# DS131-1_0-BpH.net
KiCad netlist of a schematic drawn in Altium Designer
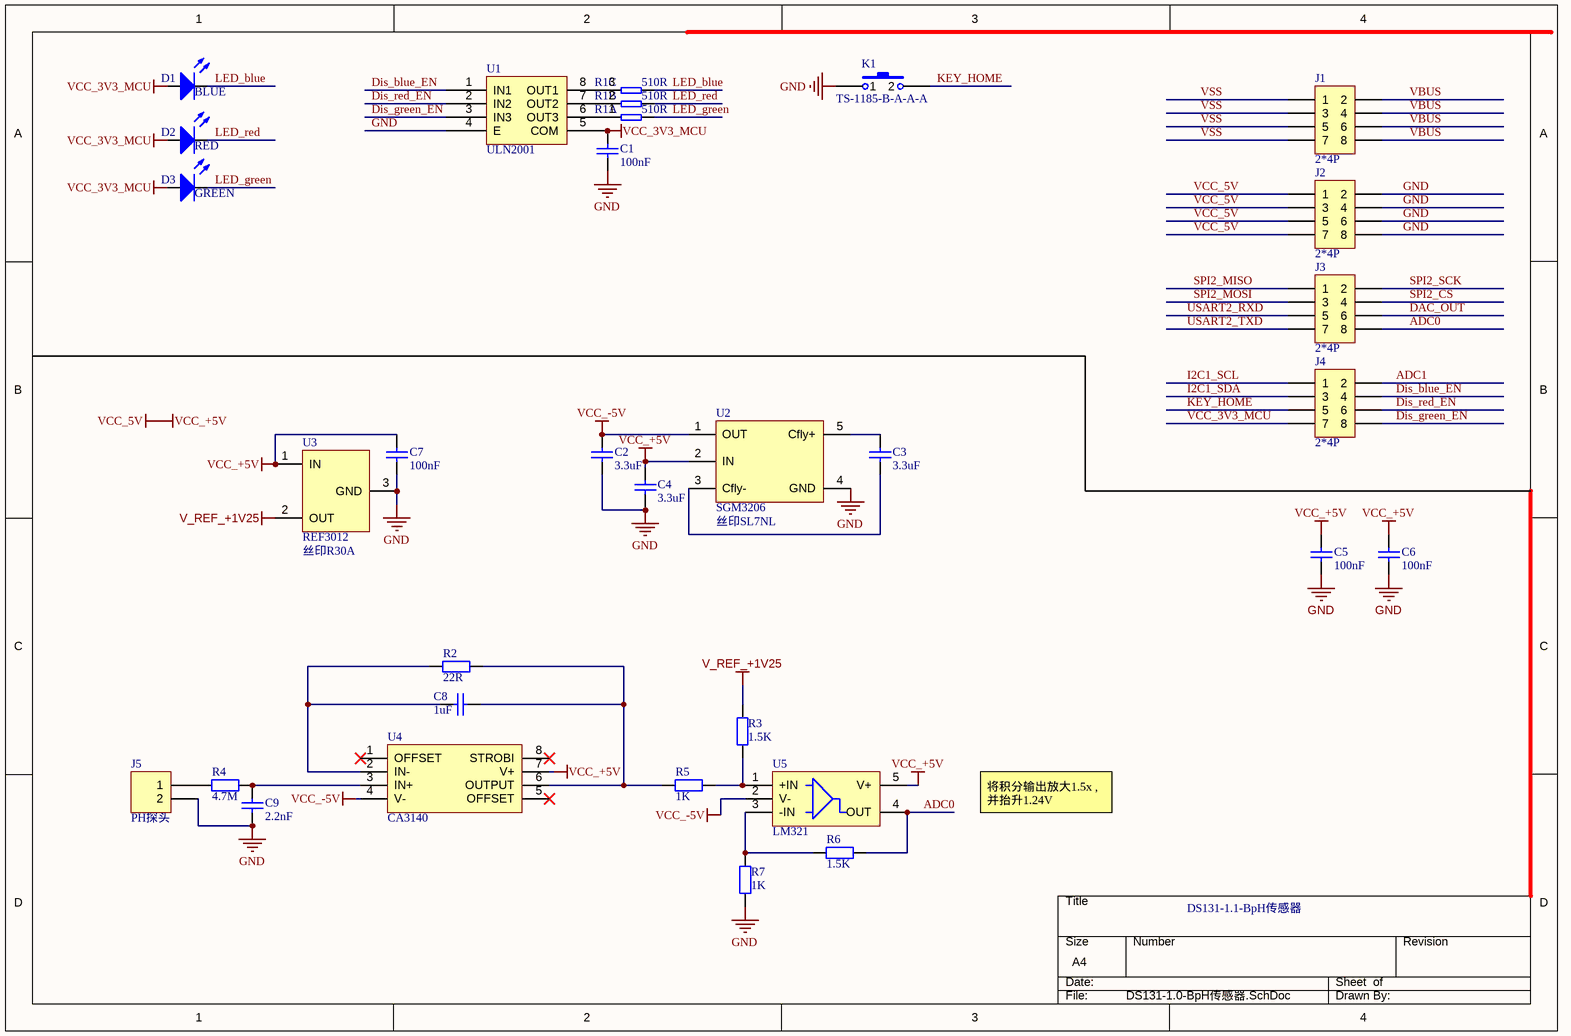
[diagram p0: DS131-1.0-BpH传感器.SchDoc]

(export (version "E")
  (design (tool "Eeschema 10.0.6"))
  (components
    (comp (ref "C1")
      (value "100nF")
      (footprint "0603CAP")
      (description "贴片电容")
      (fields (field (name "Comment") "SMDCAP00013"))
      (libsource (lib "AD_SCH") (part "MLCC 100nF 50V ±10％ 0603"))
    )
    (comp (ref "C2")
      (value "3.3uF")
      (footprint "0603CAP")
      (description "贴片电容")
      (fields (field (name "Comment") "MLCC 3.3uF 50V ±10％ 0603"))
      (libsource (lib "AD_SCH") (part "MLCC 3.3uF 50V ±10％ 0603"))
    )
    (comp (ref "C3")
      (value "3.3uF")
      (footprint "0603CAP")
      (description "贴片电容")
      (fields (field (name "Comment") "MLCC 3.3uF 50V ±10％ 0603"))
      (libsource (lib "AD_SCH") (part "MLCC 3.3uF 50V ±10％ 0603"))
    )
    (comp (ref "C4")
      (value "3.3uF")
      (footprint "0603CAP")
      (description "贴片电容")
      (fields (field (name "Comment") "MLCC 3.3uF 50V ±10％ 0603"))
      (libsource (lib "AD_SCH") (part "MLCC 3.3uF 50V ±10％ 0603"))
    )
    (comp (ref "C5")
      (value "100nF")
      (footprint "0603CAP")
      (description "贴片电容")
      (fields (field (name "Comment") "SMDCAP00013"))
      (libsource (lib "AD_SCH") (part "MLCC 100nF 50V ±10％ 0603"))
    )
    (comp (ref "C6")
      (value "100nF")
      (footprint "0603CAP")
      (description "贴片电容")
      (fields (field (name "Comment") "SMDCAP00013"))
      (libsource (lib "AD_SCH") (part "MLCC 100nF 50V ±10％ 0603"))
    )
    (comp (ref "C7")
      (value "100nF")
      (footprint "0603CAP")
      (description "贴片电容")
      (fields (field (name "Comment") "SMDCAP00013"))
      (libsource (lib "AD_SCH") (part "MLCC 100nF 50V ±10％ 0603"))
    )
    (comp (ref "C8")
      (value "1uF")
      (footprint "0603CAP")
      (description "贴片电容")
      (fields (field (name "Comment") "SMDCAP00015"))
      (libsource (lib "AD_SCH") (part "MLCC 1uF 50V ±10％ 0603"))
    )
    (comp (ref "C9")
      (value "2.2nF")
      (footprint "0603CAP")
      (description "贴片电容")
      (libsource (lib "AD_SCH") (part "MLCC 2.2nF 50V ±10％ 0603"))
    )
    (comp (ref "D1")
      (value "BLUE")
      (footprint "LED_0805")
      (description "贴片LED")
      (fields (field (name "Comment") "SMDLED00010"))
      (libsource (lib "AD_SCH") (part "Chip 蓝色LED 0805"))
    )
    (comp (ref "D2")
      (value "RED")
      (footprint "LED_0805")
      (description "贴片LED")
      (fields (field (name "Comment") "SMDLED00003"))
      (libsource (lib "AD_SCH") (part "Chip 红色LED 0805"))
    )
    (comp (ref "D3")
      (value "GREEN")
      (footprint "LED_0805")
      (description "贴片LED")
      (fields (field (name "Comment") "Chip 翠绿LED 0805"))
      (libsource (lib "AD_SCH") (part "Chip 翠绿LED 0805"))
    )
    (comp (ref "J1")
      (value "2*4P")
      (footprint "X1321WVS-2x04J-C40D53")
      (description "双排针2x4P 立贴 1.27mm")
      (fields (field (name "Comment") "X1321WVS-2x04J-C40D53"))
      (libsource (lib "AD_SCH") (part "X1321WVS-2x04J-C40D53"))
    )
    (comp (ref "J2")
      (value "2*4P")
      (footprint "X1321WVS-2x04J-C40D53")
      (description "双排针2x4P 立贴 1.27mm")
      (fields (field (name "Comment") "X1321WVS-2x04J-C40D53"))
      (libsource (lib "AD_SCH") (part "X1321WVS-2x04J-C40D53"))
    )
    (comp (ref "J3")
      (value "2*4P")
      (footprint "X1321WVS-2x04J-C40D53")
      (description "双排针2x4P 立贴 1.27mm")
      (fields (field (name "Comment") "X1321WVS-2x04J-C40D53"))
      (libsource (lib "AD_SCH") (part "X1321WVS-2x04J-C40D53"))
    )
    (comp (ref "J4")
      (value "2*4P")
      (footprint "X1321WVS-2x04J-C40D53")
      (description "双排针2x4P 立贴 1.27mm")
      (fields (field (name "Comment") "X1321WVS-2x04J-C40D53"))
      (libsource (lib "AD_SCH") (part "X1321WVS-2x04J-C40D53"))
    )
    (comp (ref "J5")
      (value "PH探头")
      (footprint "SIP2")
      (description "单排直针")
      (fields (field (name "Comment") "SL000000042"))
      (libsource (lib "AD_SCH") (part "DIP2 单排直针 1*40P 间距2.54mm 针长11mm 铜"))
    )
    (comp (ref "K1")
      (value "TS-1185-B-A-A-A")
      (footprint "KEY_TS-1185-x-A-A-A")
      (description "轻触开关")
      (libsource (lib "AD_SCH") (part "TS-1185-B-A-A-A"))
    )
    (comp (ref "R1")
      (value "510R")
      (footprint "0603RES_Pack4")
      (description "贴片排阻")
      (fields (field (name "Comment") "SMDRES05003"))
      (libsource (lib "AD_SCH") (part "Chip R*4 510R 1/16W ±5％ 0603"))
    )
    (comp (ref "R2")
      (value "22R")
      (footprint "0603RES")
      (description "贴片电阻")
      (libsource (lib "AD_SCH") (part "Chip 22R 1/16W ±1％ 0603"))
    )
    (comp (ref "R3")
      (value "1.5K")
      (footprint "0603RES")
      (description "贴片电阻")
      (fields (field (name "Comment") "SMDRES00039"))
      (libsource (lib "") (part "Chip 1.5K 1/16W ±1％ 0603_1"))
    )
    (comp (ref "R4")
      (value "4.7M")
      (footprint "0603RES")
      (description "贴片电阻")
      (fields (field (name "Comment") "Chip 4.7M 1/16W ±1％ 0603"))
      (libsource (lib "AD_SCH") (part "Chip 4.7M 1/16W ±1％ 0603"))
    )
    (comp (ref "R5")
      (value "1K")
      (footprint "0603RES")
      (description "贴片电阻")
      (fields (field (name "Comment") "SMDRES00034"))
      (libsource (lib "AD_SCH") (part "Chip 1K 1/16W ±1％ 0603"))
    )
    (comp (ref "R6")
      (value "1.5K")
      (footprint "0603RES")
      (description "贴片电阻")
      (fields (field (name "Comment") "SMDRES00039"))
      (libsource (lib "AD_SCH") (part "Chip 1.5K 1/16W ±1％ 0603"))
    )
    (comp (ref "R7")
      (value "1K")
      (footprint "0603RES")
      (description "贴片电阻")
      (fields (field (name "Comment") "SMDRES00034"))
      (libsource (lib "") (part "Chip 1K 1/16W ±1％ 0603_1"))
    )
    (comp (ref "U1")
      (value "ULN2001")
      (footprint "SO-8")
      (description "电机驱动芯片")
      (fields (field (name "Comment") "SMDIC000018"))
      (libsource (lib "AD_SCH") (part "ULN2001 SOP-8"))
    )
    (comp (ref "U2")
      (value "SGM3206")
      (footprint "SOT23-5")
      (description "SGMICRO(圣邦微)\r\nSGM3206YN5G/TR\r\nSOT-23-5")
      (fields (field (name "ALTIUM_VALUE") "丝印SL7NL"))
      (libsource (lib "AD_SCH") (part "SGM3206"))
    )
    (comp (ref "U3")
      (value "REF3012")
      (footprint "SOT23")
      (description "TI\r\nREF3012AIDBZR\r\nSOT-23")
      (fields (field (name "ALTIUM_VALUE") "丝印R30A"))
      (libsource (lib "AD_SCH") (part "REF3012"))
    )
    (comp (ref "U4")
      (value "CA3140")
      (footprint "SO-8")
      (description "RENESAS(瑞萨)\r\nCA3140AMZ96\r\nSOIC-8")
      (libsource (lib "AD_SCH") (part "CA3140"))
    )
    (comp (ref "U5")
      (value "LM321")
      (footprint "SOT23-5")
      (description "TI\r\nLM321MFX/NOPB\r\nSOT-23-5")
      (fields (field (name "Comment") "SMDIC000035"))
      (libsource (lib "AD_SCH") (part "LM321 SOT23-5"))
    )
  )
  (nets
    (net (code "1") (name "/ADC0") (class "Default")
      (node (ref "J3") (pin "8") (pinfunction "8_8") (pintype "passive"))
      (node (ref "R6") (pin "2") (pinfunction "2_2") (pintype "passive"))
      (node (ref "U5") (pin "4") (pinfunction "OUT_4") (pintype "passive"))
    )
    (net (code "2") (name "/ADC1") (class "Default")
      (node (ref "J4") (pin "2") (pinfunction "2_2") (pintype "passive"))
    )
    (net (code "3") (name "/DAC_OUT") (class "Default")
      (node (ref "J3") (pin "6") (pinfunction "6_6") (pintype "passive"))
    )
    (net (code "4") (name "/Dis_blue_EN") (class "Default")
      (node (ref "J4") (pin "4") (pinfunction "4_4") (pintype "passive"))
      (node (ref "U1") (pin "1") (pinfunction "IN1_1") (pintype "passive"))
    )
    (net (code "5") (name "/Dis_green_EN") (class "Default")
      (node (ref "J4") (pin "8") (pinfunction "8_8") (pintype "passive"))
      (node (ref "U1") (pin "3") (pinfunction "IN3_3") (pintype "passive"))
    )
    (net (code "6") (name "/Dis_red_EN") (class "Default")
      (node (ref "J4") (pin "6") (pinfunction "6_6") (pintype "passive"))
      (node (ref "U1") (pin "2") (pinfunction "IN2_2") (pintype "passive"))
    )
    (net (code "7") (name "/I2C1_SCL") (class "Default")
      (node (ref "J4") (pin "1") (pinfunction "1_1") (pintype "passive"))
    )
    (net (code "8") (name "/I2C1_SDA") (class "Default")
      (node (ref "J4") (pin "3") (pinfunction "3_3") (pintype "passive"))
    )
    (net (code "9") (name "/KEY_HOME") (class "Default")
      (node (ref "J4") (pin "5") (pinfunction "5_5") (pintype "passive"))
      (node (ref "K1") (pin "2") (pinfunction "2_2") (pintype "passive"))
    )
    (net (code "10") (name "/LED_blue") (class "Default")
      (node (ref "D1") (pin "2") (pinfunction "K_2") (pintype "passive"))
      (node (ref "R1") (pin "6") (pinfunction "6_6") (pintype "passive"))
    )
    (net (code "11") (name "/LED_green") (class "Default")
      (node (ref "D3") (pin "2") (pinfunction "K_2") (pintype "passive"))
      (node (ref "R1") (pin "8") (pinfunction "8_8") (pintype "passive"))
    )
    (net (code "12") (name "/LED_red") (class "Default")
      (node (ref "D2") (pin "2") (pinfunction "K_2") (pintype "passive"))
      (node (ref "R1") (pin "7") (pinfunction "7_7") (pintype "passive"))
    )
    (net (code "13") (name "/SPI2_CS") (class "Default")
      (node (ref "J3") (pin "4") (pinfunction "4_4") (pintype "passive"))
    )
    (net (code "14") (name "/SPI2_MISO") (class "Default")
      (node (ref "J3") (pin "1") (pinfunction "1_1") (pintype "passive"))
    )
    (net (code "15") (name "/SPI2_MOSI") (class "Default")
      (node (ref "J3") (pin "3") (pinfunction "3_3") (pintype "passive"))
    )
    (net (code "16") (name "/SPI2_SCK") (class "Default")
      (node (ref "J3") (pin "2") (pinfunction "2_2") (pintype "passive"))
    )
    (net (code "17") (name "/USART2_RXD") (class "Default")
      (node (ref "J3") (pin "5") (pinfunction "5_5") (pintype "passive"))
    )
    (net (code "18") (name "/USART2_TXD") (class "Default")
      (node (ref "J3") (pin "7") (pinfunction "7_7") (pintype "passive"))
    )
    (net (code "19") (name "/VBUS") (class "Default")
      (node (ref "J1") (pin "2") (pinfunction "2_2") (pintype "passive"))
      (node (ref "J1") (pin "4") (pinfunction "4_4") (pintype "passive"))
      (node (ref "J1") (pin "6") (pinfunction "6_6") (pintype "passive"))
      (node (ref "J1") (pin "8") (pinfunction "8_8") (pintype "passive"))
    )
    (net (code "20") (name "/VSS") (class "Default")
      (node (ref "J1") (pin "1") (pinfunction "1_1") (pintype "passive"))
      (node (ref "J1") (pin "3") (pinfunction "3_3") (pintype "passive"))
      (node (ref "J1") (pin "5") (pinfunction "5_5") (pintype "passive"))
      (node (ref "J1") (pin "7") (pinfunction "7_7") (pintype "passive"))
    )
    (net (code "21") (name "GND") (class "Default")
      (node (ref "C1") (pin "1") (pinfunction "1_1") (pintype "passive"))
      (node (ref "C2") (pin "1") (pinfunction "1_1") (pintype "passive"))
      (node (ref "C4") (pin "2") (pinfunction "2_2") (pintype "passive"))
      (node (ref "C5") (pin "1") (pinfunction "1_1") (pintype "passive"))
      (node (ref "C6") (pin "1") (pinfunction "1_1") (pintype "passive"))
      (node (ref "C7") (pin "1") (pinfunction "1_1") (pintype "passive"))
      (node (ref "C9") (pin "1") (pinfunction "1_1") (pintype "passive"))
      (node (ref "J2") (pin "2") (pinfunction "2_2") (pintype "passive"))
      (node (ref "J2") (pin "4") (pinfunction "4_4") (pintype "passive"))
      (node (ref "J2") (pin "6") (pinfunction "6_6") (pintype "passive"))
      (node (ref "J2") (pin "8") (pinfunction "8_8") (pintype "passive"))
      (node (ref "J5") (pin "2") (pinfunction "2_2") (pintype "passive"))
      (node (ref "K1") (pin "1") (pinfunction "1_1") (pintype "passive"))
      (node (ref "R7") (pin "1") (pinfunction "1_1") (pintype "passive"))
      (node (ref "U1") (pin "4") (pinfunction "E_4") (pintype "passive"))
      (node (ref "U2") (pin "4") (pinfunction "GND_4") (pintype "passive"))
      (node (ref "U3") (pin "3") (pinfunction "GND_3") (pintype "passive"))
    )
    (net (code "22") (name "Net-(J5-Pad1)") (class "Default")
      (node (ref "J5") (pin "1") (pinfunction "1_1") (pintype "passive"))
      (node (ref "R4") (pin "1") (pinfunction "1_1") (pintype "passive"))
    )
    (net (code "23") (name "Net-(U1-OUT1)") (class "Default")
      (node (ref "R1") (pin "3") (pinfunction "3_3") (pintype "passive"))
      (node (ref "U1") (pin "8") (pinfunction "OUT1_8") (pintype "passive"))
    )
    (net (code "24") (name "Net-(U1-OUT2)") (class "Default")
      (node (ref "R1") (pin "2") (pinfunction "2_2") (pintype "passive"))
      (node (ref "U1") (pin "7") (pinfunction "OUT2_7") (pintype "passive"))
    )
    (net (code "25") (name "Net-(U1-OUT3)") (class "Default")
      (node (ref "R1") (pin "1") (pinfunction "1_1") (pintype "passive"))
      (node (ref "U1") (pin "6") (pinfunction "OUT3_6") (pintype "passive"))
    )
    (net (code "26") (name "Net-(U2-Cfly+)") (class "Default")
      (node (ref "C3") (pin "1") (pinfunction "1_1") (pintype "passive"))
      (node (ref "U2") (pin "5") (pinfunction "Cfly+_5") (pintype "passive"))
    )
    (net (code "27") (name "Net-(U2-Cfly-)") (class "Default")
      (node (ref "C3") (pin "2") (pinfunction "2_2") (pintype "passive"))
      (node (ref "U2") (pin "3") (pinfunction "Cfly-_3") (pintype "passive"))
    )
    (net (code "28") (name "Net-(U4-IN+)") (class "Default")
      (node (ref "C9") (pin "2") (pinfunction "2_2") (pintype "passive"))
      (node (ref "R4") (pin "2") (pinfunction "2_2") (pintype "passive"))
      (node (ref "U4") (pin "3") (pinfunction "IN+_3") (pintype "passive"))
    )
    (net (code "29") (name "Net-(U4-IN-)") (class "Default")
      (node (ref "C8") (pin "1") (pinfunction "1_1") (pintype "passive"))
      (node (ref "R2") (pin "1") (pinfunction "1_1") (pintype "passive"))
      (node (ref "U4") (pin "2") (pinfunction "IN-_2") (pintype "passive"))
    )
    (net (code "30") (name "Net-(U4-OUTPUT)") (class "Default")
      (node (ref "C8") (pin "2") (pinfunction "2_2") (pintype "passive"))
      (node (ref "R2") (pin "2") (pinfunction "2_2") (pintype "passive"))
      (node (ref "R5") (pin "1") (pinfunction "1_1") (pintype "passive"))
      (node (ref "U4") (pin "6") (pinfunction "OUTPUT_6") (pintype "passive"))
    )
    (net (code "31") (name "Net-(U5-+IN)") (class "Default")
      (node (ref "R3") (pin "2") (pinfunction "2_2") (pintype "passive"))
      (node (ref "R5") (pin "2") (pinfunction "2_2") (pintype "passive"))
      (node (ref "U5") (pin "1") (pinfunction "+IN_1") (pintype "passive"))
    )
    (net (code "32") (name "Net-(U5--IN)") (class "Default")
      (node (ref "R6") (pin "1") (pinfunction "1_1") (pintype "passive"))
      (node (ref "R7") (pin "2") (pinfunction "2_2") (pintype "passive"))
      (node (ref "U5") (pin "3") (pinfunction "-IN_3") (pintype "passive"))
    )
    (net (code "33") (name "VCC_+5V") (class "Default")
      (node (ref "C4") (pin "1") (pinfunction "1_1") (pintype "passive"))
      (node (ref "C5") (pin "2") (pinfunction "2_2") (pintype "passive"))
      (node (ref "C6") (pin "2") (pinfunction "2_2") (pintype "passive"))
      (node (ref "C7") (pin "2") (pinfunction "2_2") (pintype "passive"))
      (node (ref "J2") (pin "1") (pinfunction "1_1") (pintype "passive"))
      (node (ref "J2") (pin "3") (pinfunction "3_3") (pintype "passive"))
      (node (ref "J2") (pin "5") (pinfunction "5_5") (pintype "passive"))
      (node (ref "J2") (pin "7") (pinfunction "7_7") (pintype "passive"))
      (node (ref "U2") (pin "2") (pinfunction "IN_2") (pintype "passive"))
      (node (ref "U3") (pin "1") (pinfunction "IN_1") (pintype "passive"))
      (node (ref "U4") (pin "7") (pinfunction "V+_7") (pintype "passive"))
      (node (ref "U5") (pin "5") (pinfunction "V+_5") (pintype "passive"))
    )
    (net (code "34") (name "VCC_-5V") (class "Default")
      (node (ref "C2") (pin "2") (pinfunction "2_2") (pintype "passive"))
      (node (ref "U2") (pin "1") (pinfunction "OUT_1") (pintype "passive"))
      (node (ref "U4") (pin "4") (pinfunction "V-_4") (pintype "passive"))
      (node (ref "U5") (pin "2") (pinfunction "V-_2") (pintype "passive"))
    )
    (net (code "35") (name "VCC_3V3_MCU") (class "Default")
      (node (ref "C1") (pin "2") (pinfunction "2_2") (pintype "passive"))
      (node (ref "D1") (pin "1") (pinfunction "A_1") (pintype "passive"))
      (node (ref "D2") (pin "1") (pinfunction "A_1") (pintype "passive"))
      (node (ref "D3") (pin "1") (pinfunction "A_1") (pintype "passive"))
      (node (ref "J4") (pin "7") (pinfunction "7_7") (pintype "passive"))
      (node (ref "U1") (pin "5") (pinfunction "COM_5") (pintype "passive"))
    )
    (net (code "36") (name "V_REF_+1V25") (class "Default")
      (node (ref "R3") (pin "1") (pinfunction "1_1") (pintype "passive"))
      (node (ref "U3") (pin "2") (pinfunction "OUT_2") (pintype "passive"))
    )
    (net (code "37") (name "unconnected-(U4-OFFSET-Pad1)") (class "Default")
      (node (ref "U4") (pin "1") (pinfunction "OFFSET_1") (pintype "passive+no_connect"))
    )
    (net (code "38") (name "unconnected-(U4-OFFSET-Pad5)") (class "Default")
      (node (ref "U4") (pin "5") (pinfunction "OFFSET_5") (pintype "passive+no_connect"))
    )
    (net (code "39") (name "unconnected-(U4-STROBI-Pad8)") (class "Default")
      (node (ref "U4") (pin "8") (pinfunction "STROBI_8") (pintype "passive+no_connect"))
    )
  )
)
